# rs422-selectable.net
KiCad netlist of a schematic drawn in Altium Designer
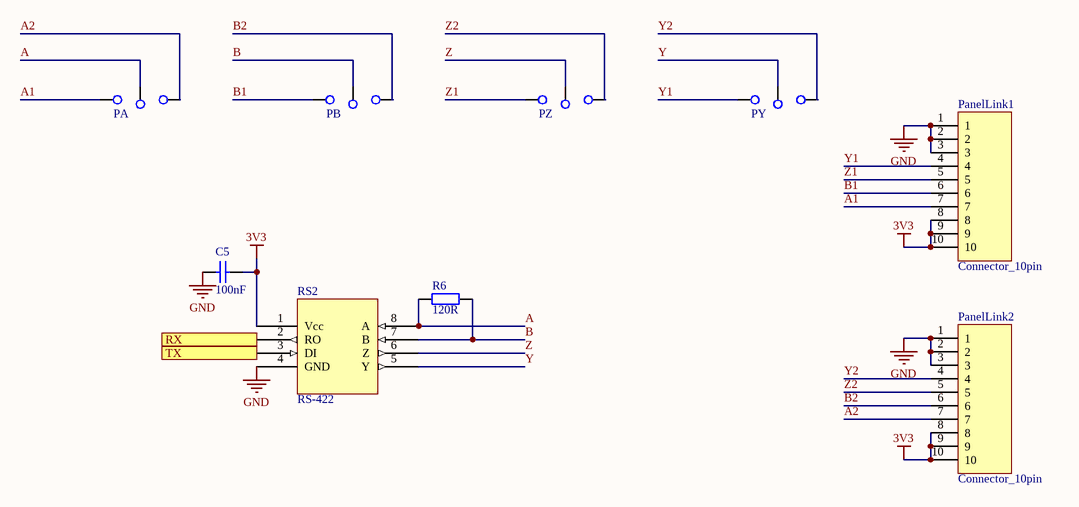
[diagram p0: rs422-selectable.SchDoc]

(export (version "E")
  (design (tool "Eeschema 10.0.6"))
  (components
    (comp (ref "C5")
      (value "100nF")
      (footprint "FP_0805_CAP_085")
      (description "Capacitor")
      (fields (field (name "TOLERANCE") "+80%/-20%") (field (name "VOLTAGE") "25V"))
      (libsource (lib "hallglib") (part "CAP 100nF"))
    )
    (comp (ref "PA") (value "PA") (footprint "JUMPER_3") (libsource (lib "mylib") (part "JUMPER_3")))
    (comp (ref "PanelLink1")
      (value "Connector_10pin")
      (footprint "FP_CONN10_SZK_ALLO")
      (libsource (lib "hallglib") (part "Connector_10pin"))
    )
    (comp (ref "PanelLink2")
      (value "Connector_10pin")
      (footprint "FP_CONN10_SZK_ALLO")
      (libsource (lib "hallglib") (part "Connector_10pin"))
    )
    (comp (ref "PB") (value "PB") (footprint "JUMPER_3") (libsource (lib "mylib") (part "JUMPER_3")))
    (comp (ref "PY") (value "PY") (footprint "JUMPER_3") (libsource (lib "mylib") (part "JUMPER_3")))
    (comp (ref "PZ") (value "PZ") (footprint "JUMPER_3") (libsource (lib "mylib") (part "JUMPER_3")))
    (comp (ref "R6")
      (value "120R")
      (footprint "FP_0805_RES")
      (description "Resistor")
      (fields (field (name "TOLERANCE") "5%") (field (name "POWER") "125mW"))
      (libsource (lib "hallglib") (part "RES 120R"))
    )
    (comp (ref "RS2")
      (value "RS-422")
      (footprint "NSOIC-8")
      (description "RS-422 transceiver 3V3")
      (libsource (lib "mylib") (part "ISL83071"))
    )
  )
  (nets
    (net (code "1") (name "/A") (class "Default")
      (node (ref "PA") (pin "2") (pinfunction "Cmid_2") (pintype "passive"))
      (node (ref "R6") (pin "1") (pinfunction "1_1") (pintype "passive"))
      (node (ref "RS2") (pin "8") (pinfunction "A_8") (pintype "input"))
    )
    (net (code "2") (name "/A1") (class "Default")
      (node (ref "PA") (pin "1") (pinfunction "C1_1") (pintype "passive"))
      (node (ref "PanelLink1") (pin "7") (pinfunction "7_7") (pintype "passive"))
    )
    (net (code "3") (name "/A2") (class "Default")
      (node (ref "PA") (pin "3") (pinfunction "C2_3") (pintype "passive"))
      (node (ref "PanelLink2") (pin "7") (pinfunction "7_7") (pintype "passive"))
    )
    (net (code "4") (name "/B") (class "Default")
      (node (ref "PB") (pin "2") (pinfunction "Cmid_2") (pintype "passive"))
      (node (ref "R6") (pin "2") (pinfunction "2_2") (pintype "passive"))
      (node (ref "RS2") (pin "7") (pinfunction "B_7") (pintype "input"))
    )
    (net (code "5") (name "/B1") (class "Default")
      (node (ref "PB") (pin "1") (pinfunction "C1_1") (pintype "passive"))
      (node (ref "PanelLink1") (pin "6") (pinfunction "6_6") (pintype "passive"))
    )
    (net (code "6") (name "/B2") (class "Default")
      (node (ref "PB") (pin "3") (pinfunction "C2_3") (pintype "passive"))
      (node (ref "PanelLink2") (pin "6") (pinfunction "6_6") (pintype "passive"))
    )
    (net (code "7") (name "/RX") (class "Default")
      (node (ref "RS2") (pin "2") (pinfunction "RO_2") (pintype "output"))
    )
    (net (code "8") (name "/TX") (class "Default")
      (node (ref "RS2") (pin "3") (pinfunction "DI_3") (pintype "input"))
    )
    (net (code "9") (name "/Y") (class "Default")
      (node (ref "PY") (pin "2") (pinfunction "Cmid_2") (pintype "passive"))
      (node (ref "RS2") (pin "5") (pinfunction "Y_5") (pintype "output"))
    )
    (net (code "10") (name "/Y1") (class "Default")
      (node (ref "PY") (pin "1") (pinfunction "C1_1") (pintype "passive"))
      (node (ref "PanelLink1") (pin "4") (pinfunction "4_4") (pintype "passive"))
    )
    (net (code "11") (name "/Y2") (class "Default")
      (node (ref "PY") (pin "3") (pinfunction "C2_3") (pintype "passive"))
      (node (ref "PanelLink2") (pin "4") (pinfunction "4_4") (pintype "passive"))
    )
    (net (code "12") (name "/Z") (class "Default")
      (node (ref "PZ") (pin "2") (pinfunction "Cmid_2") (pintype "passive"))
      (node (ref "RS2") (pin "6") (pinfunction "Z_6") (pintype "output"))
    )
    (net (code "13") (name "/Z1") (class "Default")
      (node (ref "PZ") (pin "1") (pinfunction "C1_1") (pintype "passive"))
      (node (ref "PanelLink1") (pin "5") (pinfunction "5_5") (pintype "passive"))
    )
    (net (code "14") (name "/Z2") (class "Default")
      (node (ref "PZ") (pin "3") (pinfunction "C2_3") (pintype "passive"))
      (node (ref "PanelLink2") (pin "5") (pinfunction "5_5") (pintype "passive"))
    )
    (net (code "15") (name "3V3") (class "Default")
      (node (ref "C5") (pin "1") (pinfunction "1_1") (pintype "passive"))
      (node (ref "PanelLink1") (pin "10") (pinfunction "10_10") (pintype "passive"))
      (node (ref "PanelLink1") (pin "8") (pinfunction "8_8") (pintype "passive"))
      (node (ref "PanelLink1") (pin "9") (pinfunction "9_9") (pintype "passive"))
      (node (ref "PanelLink2") (pin "10") (pinfunction "10_10") (pintype "passive"))
      (node (ref "PanelLink2") (pin "8") (pinfunction "8_8") (pintype "passive"))
      (node (ref "PanelLink2") (pin "9") (pinfunction "9_9") (pintype "passive"))
      (node (ref "RS2") (pin "1") (pinfunction "Vcc_1") (pintype "power_in"))
    )
    (net (code "16") (name "GND") (class "Default")
      (node (ref "C5") (pin "2") (pinfunction "2_2") (pintype "passive"))
      (node (ref "PanelLink1") (pin "1") (pinfunction "1_1") (pintype "passive"))
      (node (ref "PanelLink1") (pin "2") (pinfunction "2_2") (pintype "passive"))
      (node (ref "PanelLink1") (pin "3") (pinfunction "3_3") (pintype "passive"))
      (node (ref "PanelLink2") (pin "1") (pinfunction "1_1") (pintype "passive"))
      (node (ref "PanelLink2") (pin "2") (pinfunction "2_2") (pintype "passive"))
      (node (ref "PanelLink2") (pin "3") (pinfunction "3_3") (pintype "passive"))
      (node (ref "RS2") (pin "4") (pinfunction "GND_4") (pintype "power_in"))
    )
  )
)
